# fpgaTop.net
KiCad netlist of a schematic drawn in Altium Designer
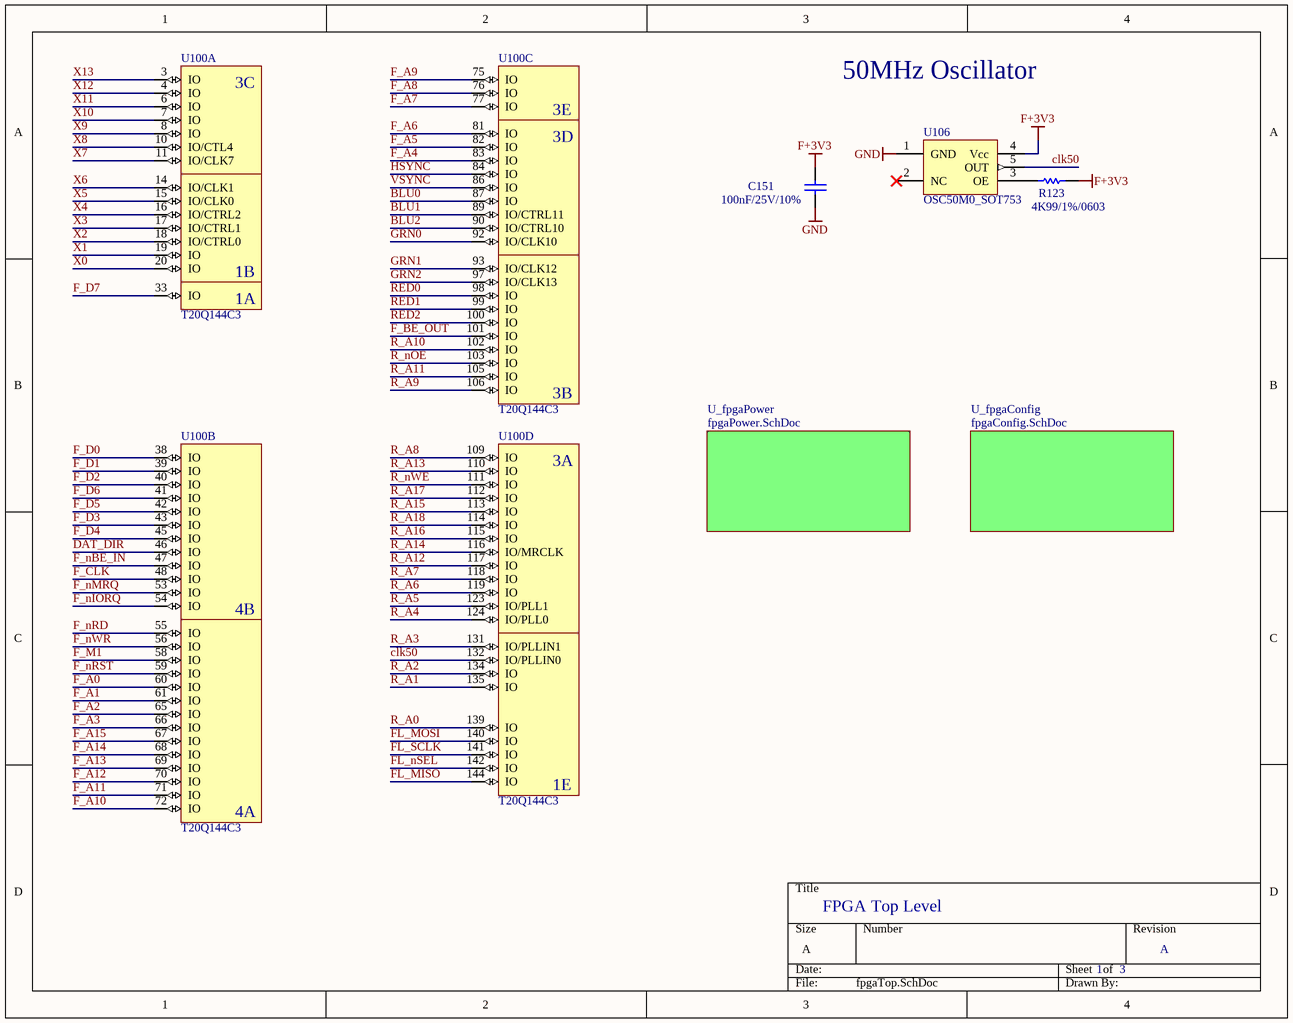
[diagram p0: fpgaTop.SchDoc]

(export (version "E")
  (design (tool "Eeschema 10.0.6"))
  (components
    (comp (ref "C151")
      (value "100nF/25V/10%")
      (footprint "MY0603")
      (description "0.1µF ±10% 25V Ceramic Capacitor X7R 0603 (1608 Metric)")
      (fields (field (name "MFG") "AVX"))
      (libsource (lib "Capacitors") (part "CAP100NF25V"))
    )
    (comp (ref "R123")
      (value "4K99/1%/0603")
      (footprint "0603")
      (description "4.99k Ohm ±1% 0.1W, 1/10W Chip Resistor 0603 (1608 Metric) Moisture Resistant Thick Film")
      (fields (field (name "MFG") "Yageo"))
      (libsource (lib "Resistors") (part "RES4K99"))
    )
    (comp (ref "U100")
      (value "T20Q144C3")
      (footprint "LQFP144")
      (description "Trion® Field Programmable Gate Array (FPGA) IC 97 1044 19728 144-LQFP")
      (fields (field (name "MFG") "Efinix"))
      (libsource (lib "DigitalIC") (part "T20Q144C3"))
    )
    (comp (ref "U106")
      (value "OSC50M0_SOT753")
      (footprint "SOT753")
      (description "50 MHz XO (Standard) HCMOS, LVCMOS Oscillator 2.5V ~ 3.3V Standby (Power Down) SC-74A, SOT-753")
      (fields (field (name "MFG") "SiTime"))
      (libsource (lib "MiscSemi") (part "OSC50M0_SOT753"))
    )
  )
  (nets
    (net (code "1") (name "/BLU0") (class "Default")
      (node (ref "U100") (pin "87") (pinfunction "IO_87") (pintype "bidirectional"))
    )
    (net (code "2") (name "/BLU1") (class "Default")
      (node (ref "U100") (pin "89") (pinfunction "IO/CTRL11_89") (pintype "bidirectional"))
    )
    (net (code "3") (name "/BLU2") (class "Default")
      (node (ref "U100") (pin "90") (pinfunction "IO/CTRL10_90") (pintype "bidirectional"))
    )
    (net (code "4") (name "/DAT_DIR") (class "Default")
      (node (ref "U100") (pin "46") (pinfunction "IO_46") (pintype "bidirectional"))
    )
    (net (code "5") (name "/FL_MISO") (class "Default")
      (node (ref "U100") (pin "144") (pinfunction "IO_144") (pintype "bidirectional"))
    )
    (net (code "6") (name "/FL_MOSI") (class "Default")
      (node (ref "U100") (pin "140") (pinfunction "IO_140") (pintype "bidirectional"))
    )
    (net (code "7") (name "/FL_SCLK") (class "Default")
      (node (ref "U100") (pin "141") (pinfunction "IO_141") (pintype "bidirectional"))
    )
    (net (code "8") (name "/FL_nSEL") (class "Default")
      (node (ref "U100") (pin "142") (pinfunction "IO_142") (pintype "bidirectional"))
    )
    (net (code "9") (name "/F_A0") (class "Default")
      (node (ref "U100") (pin "60") (pinfunction "IO_60") (pintype "bidirectional"))
    )
    (net (code "10") (name "/F_A1") (class "Default")
      (node (ref "U100") (pin "61") (pinfunction "IO_61") (pintype "bidirectional"))
    )
    (net (code "11") (name "/F_A2") (class "Default")
      (node (ref "U100") (pin "65") (pinfunction "IO_65") (pintype "bidirectional"))
    )
    (net (code "12") (name "/F_A3") (class "Default")
      (node (ref "U100") (pin "66") (pinfunction "IO_66") (pintype "bidirectional"))
    )
    (net (code "13") (name "/F_A4") (class "Default")
      (node (ref "U100") (pin "83") (pinfunction "IO_83") (pintype "bidirectional"))
    )
    (net (code "14") (name "/F_A5") (class "Default")
      (node (ref "U100") (pin "82") (pinfunction "IO_82") (pintype "bidirectional"))
    )
    (net (code "15") (name "/F_A6") (class "Default")
      (node (ref "U100") (pin "81") (pinfunction "IO_81") (pintype "bidirectional"))
    )
    (net (code "16") (name "/F_A7") (class "Default")
      (node (ref "U100") (pin "77") (pinfunction "IO_77") (pintype "bidirectional"))
    )
    (net (code "17") (name "/F_A8") (class "Default")
      (node (ref "U100") (pin "76") (pinfunction "IO_76") (pintype "bidirectional"))
    )
    (net (code "18") (name "/F_A9") (class "Default")
      (node (ref "U100") (pin "75") (pinfunction "IO_75") (pintype "bidirectional"))
    )
    (net (code "19") (name "/F_A10") (class "Default")
      (node (ref "U100") (pin "72") (pinfunction "IO_72") (pintype "bidirectional"))
    )
    (net (code "20") (name "/F_A11") (class "Default")
      (node (ref "U100") (pin "71") (pinfunction "IO_71") (pintype "bidirectional"))
    )
    (net (code "21") (name "/F_A12") (class "Default")
      (node (ref "U100") (pin "70") (pinfunction "IO_70") (pintype "bidirectional"))
    )
    (net (code "22") (name "/F_A13") (class "Default")
      (node (ref "U100") (pin "69") (pinfunction "IO_69") (pintype "bidirectional"))
    )
    (net (code "23") (name "/F_A14") (class "Default")
      (node (ref "U100") (pin "68") (pinfunction "IO_68") (pintype "bidirectional"))
    )
    (net (code "24") (name "/F_A15") (class "Default")
      (node (ref "U100") (pin "67") (pinfunction "IO_67") (pintype "bidirectional"))
    )
    (net (code "25") (name "/F_BE_OUT") (class "Default")
      (node (ref "U100") (pin "101") (pinfunction "IO_101") (pintype "bidirectional"))
    )
    (net (code "26") (name "/F_CLK") (class "Default")
      (node (ref "U100") (pin "48") (pinfunction "IO_48") (pintype "bidirectional"))
    )
    (net (code "27") (name "/F_D0") (class "Default")
      (node (ref "U100") (pin "38") (pinfunction "IO_38") (pintype "bidirectional"))
    )
    (net (code "28") (name "/F_D1") (class "Default")
      (node (ref "U100") (pin "39") (pinfunction "IO_39") (pintype "bidirectional"))
    )
    (net (code "29") (name "/F_D2") (class "Default")
      (node (ref "U100") (pin "40") (pinfunction "IO_40") (pintype "bidirectional"))
    )
    (net (code "30") (name "/F_D3") (class "Default")
      (node (ref "U100") (pin "43") (pinfunction "IO_43") (pintype "bidirectional"))
    )
    (net (code "31") (name "/F_D4") (class "Default")
      (node (ref "U100") (pin "45") (pinfunction "IO_45") (pintype "bidirectional"))
    )
    (net (code "32") (name "/F_D5") (class "Default")
      (node (ref "U100") (pin "42") (pinfunction "IO_42") (pintype "bidirectional"))
    )
    (net (code "33") (name "/F_D6") (class "Default")
      (node (ref "U100") (pin "41") (pinfunction "IO_41") (pintype "bidirectional"))
    )
    (net (code "34") (name "/F_D7") (class "Default")
      (node (ref "U100") (pin "33") (pinfunction "IO_33") (pintype "bidirectional"))
    )
    (net (code "35") (name "/F_M1") (class "Default")
      (node (ref "U100") (pin "58") (pinfunction "IO_58") (pintype "bidirectional"))
    )
    (net (code "36") (name "/F_nBE_IN") (class "Default")
      (node (ref "U100") (pin "47") (pinfunction "IO_47") (pintype "bidirectional"))
    )
    (net (code "37") (name "/F_nIORQ") (class "Default")
      (node (ref "U100") (pin "54") (pinfunction "IO_54") (pintype "bidirectional"))
    )
    (net (code "38") (name "/F_nMRQ") (class "Default")
      (node (ref "U100") (pin "53") (pinfunction "IO_53") (pintype "bidirectional"))
    )
    (net (code "39") (name "/F_nRD") (class "Default")
      (node (ref "U100") (pin "55") (pinfunction "IO_55") (pintype "bidirectional"))
    )
    (net (code "40") (name "/F_nRST") (class "Default")
      (node (ref "U100") (pin "59") (pinfunction "IO_59") (pintype "bidirectional"))
    )
    (net (code "41") (name "/F_nWR") (class "Default")
      (node (ref "U100") (pin "56") (pinfunction "IO_56") (pintype "bidirectional"))
    )
    (net (code "42") (name "/GRN0") (class "Default")
      (node (ref "U100") (pin "92") (pinfunction "IO/CLK10_92") (pintype "bidirectional"))
    )
    (net (code "43") (name "/GRN1") (class "Default")
      (node (ref "U100") (pin "93") (pinfunction "IO/CLK12_93") (pintype "bidirectional"))
    )
    (net (code "44") (name "/GRN2") (class "Default")
      (node (ref "U100") (pin "97") (pinfunction "IO/CLK13_97") (pintype "bidirectional"))
    )
    (net (code "45") (name "/HSYNC") (class "Default")
      (node (ref "U100") (pin "84") (pinfunction "IO_84") (pintype "bidirectional"))
    )
    (net (code "46") (name "/RED0") (class "Default")
      (node (ref "U100") (pin "98") (pinfunction "IO_98") (pintype "bidirectional"))
    )
    (net (code "47") (name "/RED1") (class "Default")
      (node (ref "U100") (pin "99") (pinfunction "IO_99") (pintype "bidirectional"))
    )
    (net (code "48") (name "/RED2") (class "Default")
      (node (ref "U100") (pin "100") (pinfunction "IO_100") (pintype "bidirectional"))
    )
    (net (code "49") (name "/R_A0") (class "Default")
      (node (ref "U100") (pin "139") (pinfunction "IO_139") (pintype "bidirectional"))
    )
    (net (code "50") (name "/R_A1") (class "Default")
      (node (ref "U100") (pin "135") (pinfunction "IO_135") (pintype "bidirectional"))
    )
    (net (code "51") (name "/R_A2") (class "Default")
      (node (ref "U100") (pin "134") (pinfunction "IO_134") (pintype "bidirectional"))
    )
    (net (code "52") (name "/R_A3") (class "Default")
      (node (ref "U100") (pin "131") (pinfunction "IO/PLLIN1_131") (pintype "bidirectional"))
    )
    (net (code "53") (name "/R_A4") (class "Default")
      (node (ref "U100") (pin "124") (pinfunction "IO/PLL0_124") (pintype "bidirectional"))
    )
    (net (code "54") (name "/R_A5") (class "Default")
      (node (ref "U100") (pin "123") (pinfunction "IO/PLL1_123") (pintype "bidirectional"))
    )
    (net (code "55") (name "/R_A6") (class "Default")
      (node (ref "U100") (pin "119") (pinfunction "IO_119") (pintype "bidirectional"))
    )
    (net (code "56") (name "/R_A7") (class "Default")
      (node (ref "U100") (pin "118") (pinfunction "IO_118") (pintype "bidirectional"))
    )
    (net (code "57") (name "/R_A8") (class "Default")
      (node (ref "U100") (pin "109") (pinfunction "IO_109") (pintype "bidirectional"))
    )
    (net (code "58") (name "/R_A9") (class "Default")
      (node (ref "U100") (pin "106") (pinfunction "IO_106") (pintype "bidirectional"))
    )
    (net (code "59") (name "/R_A10") (class "Default")
      (node (ref "U100") (pin "102") (pinfunction "IO_102") (pintype "bidirectional"))
    )
    (net (code "60") (name "/R_A11") (class "Default")
      (node (ref "U100") (pin "105") (pinfunction "IO_105") (pintype "bidirectional"))
    )
    (net (code "61") (name "/R_A12") (class "Default")
      (node (ref "U100") (pin "117") (pinfunction "IO_117") (pintype "bidirectional"))
    )
    (net (code "62") (name "/R_A13") (class "Default")
      (node (ref "U100") (pin "110") (pinfunction "IO_110") (pintype "bidirectional"))
    )
    (net (code "63") (name "/R_A14") (class "Default")
      (node (ref "U100") (pin "116") (pinfunction "IO/MRCLK_116") (pintype "bidirectional"))
    )
    (net (code "64") (name "/R_A15") (class "Default")
      (node (ref "U100") (pin "113") (pinfunction "IO_113") (pintype "bidirectional"))
    )
    (net (code "65") (name "/R_A16") (class "Default")
      (node (ref "U100") (pin "115") (pinfunction "IO_115") (pintype "bidirectional"))
    )
    (net (code "66") (name "/R_A17") (class "Default")
      (node (ref "U100") (pin "112") (pinfunction "IO_112") (pintype "bidirectional"))
    )
    (net (code "67") (name "/R_A18") (class "Default")
      (node (ref "U100") (pin "114") (pinfunction "IO_114") (pintype "bidirectional"))
    )
    (net (code "68") (name "/R_nOE") (class "Default")
      (node (ref "U100") (pin "103") (pinfunction "IO_103") (pintype "bidirectional"))
    )
    (net (code "69") (name "/R_nWE") (class "Default")
      (node (ref "U100") (pin "111") (pinfunction "IO_111") (pintype "bidirectional"))
    )
    (net (code "70") (name "/VSYNC") (class "Default")
      (node (ref "U100") (pin "86") (pinfunction "IO_86") (pintype "bidirectional"))
    )
    (net (code "71") (name "/X0") (class "Default")
      (node (ref "U100") (pin "20") (pinfunction "IO_20") (pintype "bidirectional"))
    )
    (net (code "72") (name "/X1") (class "Default")
      (node (ref "U100") (pin "19") (pinfunction "IO_19") (pintype "bidirectional"))
    )
    (net (code "73") (name "/X2") (class "Default")
      (node (ref "U100") (pin "18") (pinfunction "IO/CTRL0_18") (pintype "bidirectional"))
    )
    (net (code "74") (name "/X3") (class "Default")
      (node (ref "U100") (pin "17") (pinfunction "IO/CTRL1_17") (pintype "bidirectional"))
    )
    (net (code "75") (name "/X4") (class "Default")
      (node (ref "U100") (pin "16") (pinfunction "IO/CTRL2_16") (pintype "bidirectional"))
    )
    (net (code "76") (name "/X5") (class "Default")
      (node (ref "U100") (pin "15") (pinfunction "IO/CLK0_15") (pintype "bidirectional"))
    )
    (net (code "77") (name "/X6") (class "Default")
      (node (ref "U100") (pin "14") (pinfunction "IO/CLK1_14") (pintype "bidirectional"))
    )
    (net (code "78") (name "/X7") (class "Default")
      (node (ref "U100") (pin "11") (pinfunction "IO/CLK7_11") (pintype "bidirectional"))
    )
    (net (code "79") (name "/X8") (class "Default")
      (node (ref "U100") (pin "10") (pinfunction "IO/CTL4_10") (pintype "bidirectional"))
    )
    (net (code "80") (name "/X9") (class "Default")
      (node (ref "U100") (pin "8") (pinfunction "IO_8") (pintype "bidirectional"))
    )
    (net (code "81") (name "/X10") (class "Default")
      (node (ref "U100") (pin "7") (pinfunction "IO_7") (pintype "bidirectional"))
    )
    (net (code "82") (name "/X11") (class "Default")
      (node (ref "U100") (pin "6") (pinfunction "IO_6") (pintype "bidirectional"))
    )
    (net (code "83") (name "/X12") (class "Default")
      (node (ref "U100") (pin "4") (pinfunction "IO_4") (pintype "bidirectional"))
    )
    (net (code "84") (name "/X13") (class "Default")
      (node (ref "U100") (pin "3") (pinfunction "IO_3") (pintype "bidirectional"))
    )
    (net (code "85") (name "/clk50") (class "Default")
      (node (ref "U100") (pin "132") (pinfunction "IO/PLLIN0_132") (pintype "bidirectional"))
      (node (ref "U106") (pin "5") (pinfunction "OUT_5") (pintype "output"))
    )
    (net (code "86") (name "F+3V3") (class "Default")
      (node (ref "C151") (pin "2") (pinfunction "2_2") (pintype "passive"))
      (node (ref "R123") (pin "1") (pinfunction "1_1") (pintype "passive"))
      (node (ref "U106") (pin "4") (pinfunction "Vcc_4") (pintype "power_in"))
    )
    (net (code "87") (name "GND") (class "Default")
      (node (ref "C151") (pin "1") (pinfunction "1_1") (pintype "passive"))
      (node (ref "U106") (pin "1") (pinfunction "GND_1") (pintype "power_in"))
    )
    (net (code "88") (name "Net-(U106-OE)") (class "Default")
      (node (ref "R123") (pin "2") (pinfunction "2_2") (pintype "passive"))
      (node (ref "U106") (pin "3") (pinfunction "OE_3") (pintype "passive"))
    )
    (net (code "89") (name "unconnected-(U106-NC-Pad2)") (class "Default")
      (node (ref "U106") (pin "2") (pinfunction "NC_2") (pintype "power_in+no_connect"))
    )
  )
)
